# NesCat.net
KiCad netlist of a schematic drawn in Altium Designer
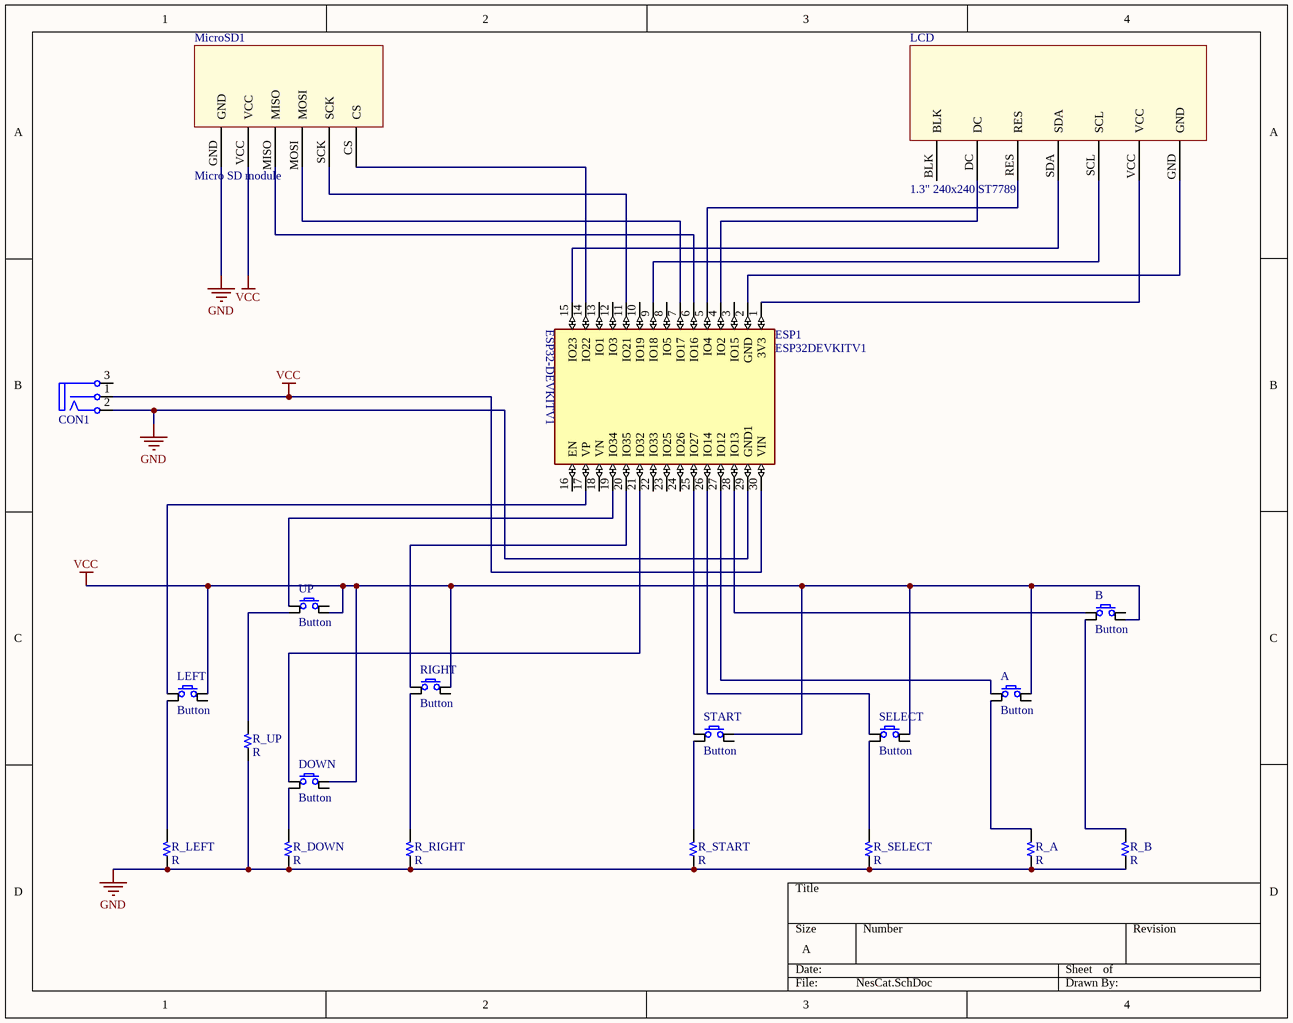
[diagram p0: NesCat.SchDoc]

(export (version "E")
  (design (tool "Eeschema 10.0.6"))
  (components
    (comp (ref "A")
      (value "Button")
      (footprint "SW/4/12mm")
      (description "Tact switch 4-pin")
      (libsource (lib "SCHlib") (part "SW SPST 4-pin"))
    )
    (comp (ref "B")
      (value "Button")
      (footprint "SW/4/12mm")
      (description "Tact switch 4-pin")
      (libsource (lib "SCHlib") (part "SW SPST 4-pin"))
    )
    (comp (ref "CON1")
      (value "CON DC PWR")
      (footprint "CONN/DC/PWR/5.0MM")
      (description "DC input connector")
      (libsource (lib "SCHlib") (part "CON DC PWR"))
    )
    (comp (ref "DOWN")
      (value "Button")
      (footprint "SW/4/12mm")
      (description "Tact switch 4-pin")
      (libsource (lib "lib") (part "SW SPST 4-pin"))
    )
    (comp (ref "ESP1")
      (value "ESP32DEVKITV1")
      (footprint "ESP32-DEVKITV1_3D")
      (fields (field (name "MF") "Do it") (field (name "MP") "ESP32 DEVKIT V1"))
      (libsource (lib "SCHlib") (part "ESP32DEVKITV1"))
    )
    (comp (ref "LCD")
      (value "1.3\" 240x240 ST7789")
      (footprint "1.3\" 240x240 ST7789")
      (libsource (lib "SCHlib") (part "1.3{dblquote} 240x240 ST7789"))
    )
    (comp (ref "LEFT")
      (value "Button")
      (footprint "SW/4/12mm")
      (description "Tact switch 4-pin")
      (libsource (lib "SCHlib") (part "SW SPST 4-pin"))
    )
    (comp (ref "MicroSD1")
      (value "Micro SD module")
      (footprint "PCBComponent_1")
      (libsource (lib "SCHlib") (part "Micro SD module"))
    )
    (comp (ref "RIGHT")
      (value "Button")
      (footprint "SW/4/12mm")
      (description "Tact switch 4-pin")
      (libsource (lib "lib") (part "SW SPST 4-pin"))
    )
    (comp (ref "R_A")
      (value "R")
      (footprint "R 1/4W/300")
      (description "Resistor")
      (libsource (lib "SCHlib") (part "Resistor"))
    )
    (comp (ref "R_B")
      (value "R")
      (footprint "R 1/4W/300")
      (description "Resistor")
      (libsource (lib "SCHlib") (part "Resistor"))
    )
    (comp (ref "R_DOWN")
      (value "R")
      (footprint "R 1/4W/300")
      (description "Resistor")
      (libsource (lib "SCHlib") (part "Resistor"))
    )
    (comp (ref "R_LEFT")
      (value "R")
      (footprint "R 1/4W/300")
      (description "Resistor")
      (libsource (lib "SCHlib") (part "Resistor"))
    )
    (comp (ref "R_RIGHT")
      (value "R")
      (footprint "R 1/4W/300")
      (description "Resistor")
      (libsource (lib "SCHlib") (part "Resistor"))
    )
    (comp (ref "R_SELECT")
      (value "R")
      (footprint "R 1/4W/300")
      (description "Resistor")
      (libsource (lib "SCHlib") (part "Resistor"))
    )
    (comp (ref "R_START")
      (value "R")
      (footprint "R 1/4W/300")
      (description "Resistor")
      (libsource (lib "SCHlib") (part "Resistor"))
    )
    (comp (ref "R_UP")
      (value "R")
      (footprint "R 1/4W/300")
      (description "Resistor")
      (libsource (lib "SCHlib") (part "Resistor"))
    )
    (comp (ref "SELECT")
      (value "Button")
      (footprint "SW/4/12mm")
      (description "Tact switch 4-pin")
      (libsource (lib "SCHlib") (part "SW SPST 4-pin"))
    )
    (comp (ref "START")
      (value "Button")
      (footprint "SW/4/12mm")
      (description "Tact switch 4-pin")
      (libsource (lib "SCHlib") (part "SW SPST 4-pin"))
    )
    (comp (ref "UP")
      (value "Button")
      (footprint "SW/4/12mm")
      (description "Tact switch 4-pin")
      (libsource (lib "SCHlib") (part "SW SPST 4-pin"))
    )
  )
  (nets
    (net (code "1") (name "GND") (class "Default")
      (node (ref "CON1") (pin "2") (pinfunction "T_2") (pintype "passive"))
      (node (ref "ESP1") (pin "29") (pinfunction "GND1_29") (pintype "bidirectional"))
      (node (ref "MicroSD1") (pin "GND") (pinfunction "GND_GND") (pintype "passive"))
      (node (ref "R_A") (pin "1") (pinfunction "1_1") (pintype "passive"))
      (node (ref "R_B") (pin "1") (pinfunction "1_1") (pintype "passive"))
      (node (ref "R_DOWN") (pin "1") (pinfunction "1_1") (pintype "passive"))
      (node (ref "R_LEFT") (pin "1") (pinfunction "1_1") (pintype "passive"))
      (node (ref "R_RIGHT") (pin "1") (pinfunction "1_1") (pintype "passive"))
      (node (ref "R_SELECT") (pin "1") (pinfunction "1_1") (pintype "passive"))
      (node (ref "R_START") (pin "1") (pinfunction "1_1") (pintype "passive"))
      (node (ref "R_UP") (pin "1") (pinfunction "1_1") (pintype "passive"))
    )
    (net (code "2") (name "Net-(A-Pad2)") (class "Default")
      (node (ref "A") (pin "2") (pinfunction "2_2") (pintype "passive"))
      (node (ref "R_A") (pin "2") (pinfunction "2_2") (pintype "passive"))
    )
    (net (code "3") (name "Net-(B-Pad2)") (class "Default")
      (node (ref "B") (pin "2") (pinfunction "2_2") (pintype "passive"))
      (node (ref "R_B") (pin "2") (pinfunction "2_2") (pintype "passive"))
    )
    (net (code "4") (name "Net-(DOWN-Pad2)") (class "Default")
      (node (ref "DOWN") (pin "2") (pinfunction "2_2") (pintype "passive"))
      (node (ref "R_DOWN") (pin "2") (pinfunction "2_2") (pintype "passive"))
    )
    (net (code "5") (name "Net-(ESP1-3V3)") (class "Default")
      (node (ref "ESP1") (pin "1") (pinfunction "3V3_1") (pintype "bidirectional"))
      (node (ref "LCD") (pin "VCC") (pinfunction "VCC_VCC") (pintype "passive"))
    )
    (net (code "6") (name "Net-(ESP1-GND)") (class "Default")
      (node (ref "ESP1") (pin "2") (pinfunction "GND_2") (pintype "bidirectional"))
      (node (ref "LCD") (pin "GND") (pinfunction "GND_GND") (pintype "passive"))
    )
    (net (code "7") (name "Net-(ESP1-IO2)") (class "Default")
      (node (ref "ESP1") (pin "4") (pinfunction "IO2_4") (pintype "bidirectional"))
      (node (ref "LCD") (pin "DC") (pinfunction "DC_DC") (pintype "passive"))
    )
    (net (code "8") (name "Net-(ESP1-IO4)") (class "Default")
      (node (ref "ESP1") (pin "5") (pinfunction "IO4_5") (pintype "bidirectional"))
      (node (ref "LCD") (pin "RES") (pinfunction "RES_RES") (pintype "passive"))
    )
    (net (code "9") (name "Net-(ESP1-IO12)") (class "Default")
      (node (ref "A") (pin "1") (pinfunction "1_1") (pintype "passive"))
      (node (ref "ESP1") (pin "27") (pinfunction "IO12_27") (pintype "bidirectional"))
    )
    (net (code "10") (name "Net-(ESP1-IO13)") (class "Default")
      (node (ref "B") (pin "1") (pinfunction "1_1") (pintype "passive"))
      (node (ref "ESP1") (pin "28") (pinfunction "IO13_28") (pintype "bidirectional"))
    )
    (net (code "11") (name "Net-(ESP1-IO14)") (class "Default")
      (node (ref "ESP1") (pin "26") (pinfunction "IO14_26") (pintype "bidirectional"))
      (node (ref "SELECT") (pin "1") (pinfunction "1_1") (pintype "passive"))
    )
    (net (code "12") (name "Net-(ESP1-IO16)") (class "Default")
      (node (ref "ESP1") (pin "6") (pinfunction "IO16_6") (pintype "bidirectional"))
      (node (ref "MicroSD1") (pin "MISO") (pinfunction "MISO_MISO") (pintype "passive"))
    )
    (net (code "13") (name "Net-(ESP1-IO17)") (class "Default")
      (node (ref "ESP1") (pin "7") (pinfunction "IO17_7") (pintype "bidirectional"))
      (node (ref "MicroSD1") (pin "MOSI") (pinfunction "MOSI_MOSI") (pintype "passive"))
    )
    (net (code "14") (name "Net-(ESP1-IO18)") (class "Default")
      (node (ref "ESP1") (pin "9") (pinfunction "IO18_9") (pintype "bidirectional"))
      (node (ref "LCD") (pin "SCL") (pinfunction "SCL_SCL") (pintype "passive"))
    )
    (net (code "15") (name "Net-(ESP1-IO21)") (class "Default")
      (node (ref "ESP1") (pin "11") (pinfunction "IO21_11") (pintype "bidirectional"))
      (node (ref "MicroSD1") (pin "SCK") (pinfunction "SCK_SCK") (pintype "passive"))
    )
    (net (code "16") (name "Net-(ESP1-IO22)") (class "Default")
      (node (ref "ESP1") (pin "14") (pinfunction "IO22_14") (pintype "bidirectional"))
      (node (ref "MicroSD1") (pin "CS") (pinfunction "CS_CS") (pintype "passive"))
    )
    (net (code "17") (name "Net-(ESP1-IO23)") (class "Default")
      (node (ref "ESP1") (pin "15") (pinfunction "IO23_15") (pintype "bidirectional"))
      (node (ref "LCD") (pin "SDA") (pinfunction "SDA_SDA") (pintype "passive"))
    )
    (net (code "18") (name "Net-(ESP1-IO27)") (class "Default")
      (node (ref "ESP1") (pin "25") (pinfunction "IO27_25") (pintype "bidirectional"))
      (node (ref "START") (pin "1") (pinfunction "1_1") (pintype "passive"))
    )
    (net (code "19") (name "Net-(ESP1-IO32)") (class "Default")
      (node (ref "DOWN") (pin "1") (pinfunction "1_1") (pintype "passive"))
      (node (ref "ESP1") (pin "21") (pinfunction "IO32_21") (pintype "bidirectional"))
    )
    (net (code "20") (name "Net-(ESP1-IO34)") (class "Default")
      (node (ref "ESP1") (pin "19") (pinfunction "IO34_19") (pintype "bidirectional"))
      (node (ref "UP") (pin "1") (pinfunction "1_1") (pintype "passive"))
    )
    (net (code "21") (name "Net-(ESP1-IO35)") (class "Default")
      (node (ref "ESP1") (pin "20") (pinfunction "IO35_20") (pintype "bidirectional"))
      (node (ref "RIGHT") (pin "1") (pinfunction "1_1") (pintype "passive"))
    )
    (net (code "22") (name "Net-(ESP1-VP)") (class "Default")
      (node (ref "ESP1") (pin "17") (pinfunction "VP_17") (pintype "bidirectional"))
      (node (ref "LEFT") (pin "1") (pinfunction "1_1") (pintype "passive"))
    )
    (net (code "23") (name "Net-(LEFT-Pad2)") (class "Default")
      (node (ref "LEFT") (pin "2") (pinfunction "2_2") (pintype "passive"))
      (node (ref "R_LEFT") (pin "2") (pinfunction "2_2") (pintype "passive"))
    )
    (net (code "24") (name "Net-(RIGHT-Pad2)") (class "Default")
      (node (ref "RIGHT") (pin "2") (pinfunction "2_2") (pintype "passive"))
      (node (ref "R_RIGHT") (pin "2") (pinfunction "2_2") (pintype "passive"))
    )
    (net (code "25") (name "Net-(R_SELECT-Pad2)") (class "Default")
      (node (ref "R_SELECT") (pin "2") (pinfunction "2_2") (pintype "passive"))
      (node (ref "SELECT") (pin "2") (pinfunction "2_2") (pintype "passive"))
    )
    (net (code "26") (name "Net-(R_START-Pad2)") (class "Default")
      (node (ref "R_START") (pin "2") (pinfunction "2_2") (pintype "passive"))
      (node (ref "START") (pin "2") (pinfunction "2_2") (pintype "passive"))
    )
    (net (code "27") (name "Net-(R_UP-Pad2)") (class "Default")
      (node (ref "R_UP") (pin "2") (pinfunction "2_2") (pintype "passive"))
      (node (ref "UP") (pin "2") (pinfunction "2_2") (pintype "passive"))
    )
    (net (code "28") (name "VCC") (class "Default")
      (node (ref "A") (pin "3") (pinfunction "3_3") (pintype "passive"))
      (node (ref "B") (pin "4") (pinfunction "4_4") (pintype "passive"))
      (node (ref "CON1") (pin "1") (pinfunction "S_1") (pintype "power_in"))
      (node (ref "DOWN") (pin "3") (pinfunction "3_3") (pintype "passive"))
      (node (ref "ESP1") (pin "30") (pinfunction "VIN_30") (pintype "bidirectional"))
      (node (ref "LEFT") (pin "3") (pinfunction "3_3") (pintype "passive"))
      (node (ref "MicroSD1") (pin "VCC") (pinfunction "VCC_VCC") (pintype "passive"))
      (node (ref "RIGHT") (pin "3") (pinfunction "3_3") (pintype "passive"))
      (node (ref "SELECT") (pin "3") (pinfunction "3_3") (pintype "passive"))
      (node (ref "START") (pin "3") (pinfunction "3_3") (pintype "passive"))
      (node (ref "UP") (pin "4") (pinfunction "4_4") (pintype "passive"))
    )
    (net (code "29") (name "unconnected-(A-Pad4)") (class "Default")
      (node (ref "A") (pin "4") (pinfunction "4_4") (pintype "passive"))
    )
    (net (code "30") (name "unconnected-(B-Pad3)") (class "Default")
      (node (ref "B") (pin "3") (pinfunction "3_3") (pintype "passive"))
    )
    (net (code "31") (name "unconnected-(CON1-TN-Pad3)") (class "Default")
      (node (ref "CON1") (pin "3") (pinfunction "TN_3") (pintype "passive"))
    )
    (net (code "32") (name "unconnected-(DOWN-Pad4)") (class "Default")
      (node (ref "DOWN") (pin "4") (pinfunction "4_4") (pintype "passive"))
    )
    (net (code "33") (name "unconnected-(ESP1-EN-Pad16)") (class "Default")
      (node (ref "ESP1") (pin "16") (pinfunction "EN_16") (pintype "bidirectional"))
    )
    (net (code "34") (name "unconnected-(ESP1-IO1-Pad13)") (class "Default")
      (node (ref "ESP1") (pin "13") (pinfunction "IO1_13") (pintype "bidirectional"))
    )
    (net (code "35") (name "unconnected-(ESP1-IO3-Pad12)") (class "Default")
      (node (ref "ESP1") (pin "12") (pinfunction "IO3_12") (pintype "bidirectional"))
    )
    (net (code "36") (name "unconnected-(ESP1-IO5-Pad8)") (class "Default")
      (node (ref "ESP1") (pin "8") (pinfunction "IO5_8") (pintype "bidirectional"))
    )
    (net (code "37") (name "unconnected-(ESP1-IO15-Pad3)") (class "Default")
      (node (ref "ESP1") (pin "3") (pinfunction "IO15_3") (pintype "bidirectional"))
    )
    (net (code "38") (name "unconnected-(ESP1-IO19-Pad10)") (class "Default")
      (node (ref "ESP1") (pin "10") (pinfunction "IO19_10") (pintype "bidirectional"))
    )
    (net (code "39") (name "unconnected-(ESP1-IO25-Pad23)") (class "Default")
      (node (ref "ESP1") (pin "23") (pinfunction "IO25_23") (pintype "bidirectional"))
    )
    (net (code "40") (name "unconnected-(ESP1-IO26-Pad24)") (class "Default")
      (node (ref "ESP1") (pin "24") (pinfunction "IO26_24") (pintype "bidirectional"))
    )
    (net (code "41") (name "unconnected-(ESP1-IO33-Pad22)") (class "Default")
      (node (ref "ESP1") (pin "22") (pinfunction "IO33_22") (pintype "bidirectional"))
    )
    (net (code "42") (name "unconnected-(ESP1-VN-Pad18)") (class "Default")
      (node (ref "ESP1") (pin "18") (pinfunction "VN_18") (pintype "bidirectional"))
    )
    (net (code "43") (name "unconnected-(LCD-PadBLK)") (class "Default")
      (node (ref "LCD") (pin "BLK") (pinfunction "BLK_BLK") (pintype "passive"))
    )
    (net (code "44") (name "unconnected-(LEFT-Pad4)") (class "Default")
      (node (ref "LEFT") (pin "4") (pinfunction "4_4") (pintype "passive"))
    )
    (net (code "45") (name "unconnected-(RIGHT-Pad4)") (class "Default")
      (node (ref "RIGHT") (pin "4") (pinfunction "4_4") (pintype "passive"))
    )
    (net (code "46") (name "unconnected-(SELECT-Pad4)") (class "Default")
      (node (ref "SELECT") (pin "4") (pinfunction "4_4") (pintype "passive"))
    )
    (net (code "47") (name "unconnected-(START-Pad4)") (class "Default")
      (node (ref "START") (pin "4") (pinfunction "4_4") (pintype "passive"))
    )
    (net (code "48") (name "unconnected-(UP-Pad3)") (class "Default")
      (node (ref "UP") (pin "3") (pinfunction "3_3") (pintype "passive"))
    )
  )
)
